# Sweep.net
KiCad netlist of a schematic drawn in Altium Designer
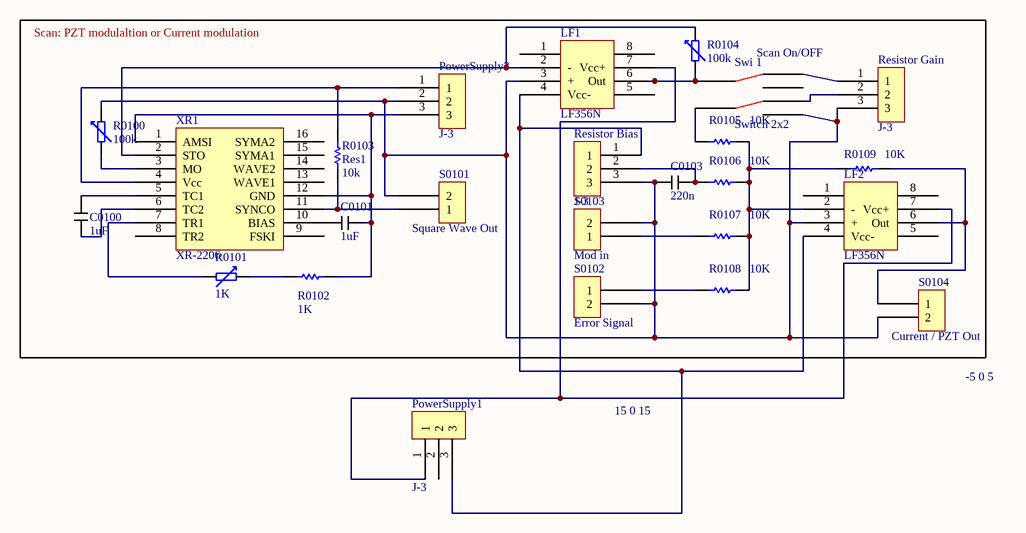
[diagram p0: Sweep.SchDoc]

(export (version "E")
  (design (tool "Eeschema 10.0.6"))
  (components
    (comp (ref "C0100") (value "1uF") (footprint "Capacitor") (libsource (lib "Schlib1") (part "Cap")))
    (comp (ref "C0101") (value "1uF") (footprint "Capacitor") (libsource (lib "Schlib1") (part "Cap")))
    (comp (ref "C0103") (value "220n") (footprint "Capacitor") (libsource (lib "Schlib1") (part "Cap")))
    (comp (ref "LF1") (value "LF356N") (footprint "DIP8") (libsource (lib "Schlib1") (part "LF356N")))
    (comp (ref "LF2") (value "LF356N") (footprint "DIP8") (libsource (lib "Schlib1") (part "LF356N")))
    (comp (ref "PowerSupply1") (value "J-3") (footprint "J3") (libsource (lib "Schlib1") (part "J-3")))
    (comp (ref "PowerSupply3") (value "J-3") (footprint "J3") (libsource (lib "") (part "J-3_2")))
    (comp (ref "R0100") (value "100k") (footprint "J3") (libsource (lib "Schlib1") (part "Res Adj")))
    (comp (ref "R0101") (value "1K") (footprint "J3") (libsource (lib "Schlib1") (part "Res Adj")))
    (comp (ref "R0102")
      (value "1K")
      (footprint "AXIAL-0.3")
      (description "Resistor")
      (fields (field (name "Comment") "Res1") (field (name "PUBLISHER") "Altium Limited"))
      (libsource (lib "Miscellaneous Devices") (part "Res1"))
    )
    (comp (ref "R0103")
      (value "Res1")
      (footprint "AXIAL-0.3")
      (description "Resistor")
      (fields (field (name "ALTIUM_VALUE") "10k") (field (name "PUBLISHER") "Altium Limited"))
      (libsource (lib "Miscellaneous Devices") (part "Res1"))
    )
    (comp (ref "R0104") (value "100k") (footprint "J3") (libsource (lib "Schlib1") (part "Res Adj")))
    (comp (ref "R0105")
      (value "10K")
      (footprint "AXIAL-0.3")
      (description "Resistor")
      (fields (field (name "Comment") "Res1") (field (name "PUBLISHER") "Altium Limited"))
      (libsource (lib "Miscellaneous Devices") (part "Res1"))
    )
    (comp (ref "R0106")
      (value "10K")
      (footprint "AXIAL-0.3")
      (description "Resistor")
      (fields (field (name "Comment") "Res1") (field (name "PUBLISHER") "Altium Limited"))
      (libsource (lib "Miscellaneous Devices") (part "Res1"))
    )
    (comp (ref "R0107")
      (value "10K")
      (footprint "AXIAL-0.3")
      (description "Resistor")
      (fields (field (name "Comment") "Res1") (field (name "PUBLISHER") "Altium Limited"))
      (libsource (lib "Miscellaneous Devices") (part "Res1"))
    )
    (comp (ref "R0108")
      (value "10K")
      (footprint "AXIAL-0.3")
      (description "Resistor")
      (fields (field (name "Comment") "Res1") (field (name "PUBLISHER") "Altium Limited"))
      (libsource (lib "Miscellaneous Devices") (part "Res1"))
    )
    (comp (ref "R0109")
      (value "10K")
      (footprint "AXIAL-0.3")
      (description "Resistor")
      (fields (field (name "Comment") "Res1") (field (name "PUBLISHER") "Altium Limited"))
      (libsource (lib "Miscellaneous Devices") (part "Res1"))
    )
    (comp (ref "Resistor Bias") (value "J-3") (footprint "J3") (libsource (lib "") (part "J-3_1")))
    (comp (ref "Resistor Gain") (value "J-3") (footprint "J3") (libsource (lib "") (part "J-3_2")))
    (comp (ref "S0101") (value "Square Wave Out") (footprint "SMA-S") (libsource (lib "") (part "SMA-S_2")))
    (comp (ref "S0102") (value "Error Signal") (footprint "SMA-S") (libsource (lib "") (part "SMA-S_3")))
    (comp (ref "S0103") (value "Mod in") (footprint "SMA-S") (libsource (lib "") (part "SMA-S_1")))
    (comp (ref "S0104")
      (value "Current / PZT Out")
      (footprint "SMA-S")
      (libsource (lib "Schlib1") (part "SMA-S"))
    )
    (comp (ref "Swi 1")
      (value "Switch 2x2")
      (footprint "Swi 2x2")
      (libsource (lib "Schlib1") (part "Switch 2x2"))
    )
    (comp (ref "XR1") (value "XR-2206") (footprint "DIP16") (libsource (lib "Schlib1") (part "XR-2206")))
  )
  (nets
    (net (code "1") (name "Net-(C0103-Pad2)") (class "Default")
      (node (ref "C0103") (pin "2") (pinfunction "2_2") (pintype "passive"))
      (node (ref "R0106") (pin "1") (pinfunction "1_1") (pintype "passive"))
      (node (ref "Resistor Bias") (pin "2") (pinfunction "2_2") (pintype "passive"))
    )
    (net (code "2") (name "Net-(LF1-+)") (class "Default")
      (node (ref "C0103") (pin "1") (pinfunction "1_1") (pintype "passive"))
      (node (ref "LF1") (pin "3") (pinfunction "+_3") (pintype "passive"))
      (node (ref "LF2") (pin "3") (pinfunction "+_3") (pintype "passive"))
      (node (ref "PowerSupply3") (pin "2") (pinfunction "2_2") (pintype "passive"))
      (node (ref "R0100") (pin "2") (pinfunction "2_2") (pintype "passive"))
      (node (ref "Resistor Bias") (pin "3") (pinfunction "3_3") (pintype "passive"))
      (node (ref "Resistor Gain") (pin "3") (pinfunction "3_3") (pintype "passive"))
      (node (ref "S0101") (pin "2") (pinfunction "2_2") (pintype "passive"))
      (node (ref "S0102") (pin "2") (pinfunction "2_2") (pintype "passive"))
      (node (ref "S0103") (pin "2") (pinfunction "2_2") (pintype "passive"))
      (node (ref "S0104") (pin "2") (pinfunction "2_2") (pintype "passive"))
      (node (ref "Swi 1") (pin "6") (pinfunction "6_6") (pintype "passive"))
    )
    (net (code "3") (name "Net-(LF1--)") (class "Default")
      (node (ref "LF1") (pin "2") (pinfunction "-_2") (pintype "passive"))
      (node (ref "R0104") (pin "2") (pinfunction "2_2") (pintype "passive"))
      (node (ref "XR1") (pin "2") (pinfunction "STO_2") (pintype "passive"))
    )
    (net (code "4") (name "Net-(LF1-Out)") (class "Default")
      (node (ref "LF1") (pin "6") (pinfunction "Out_6") (pintype "passive"))
      (node (ref "R0104") (pin "1") (pinfunction "1_1") (pintype "passive"))
      (node (ref "Swi 1") (pin "1") (pinfunction "1_1") (pintype "passive"))
    )
    (net (code "5") (name "Net-(LF1-Vcc+)") (class "Default")
      (node (ref "LF1") (pin "7") (pinfunction "Vcc+_7") (pintype "passive"))
      (node (ref "LF2") (pin "7") (pinfunction "Vcc+_7") (pintype "passive"))
      (node (ref "PowerSupply1") (pin "1") (pinfunction "1_1") (pintype "passive"))
    )
    (net (code "6") (name "Net-(LF1-Vcc-)") (class "Default")
      (node (ref "LF1") (pin "4") (pinfunction "Vcc-_4") (pintype "passive"))
      (node (ref "LF2") (pin "4") (pinfunction "Vcc-_4") (pintype "passive"))
      (node (ref "PowerSupply1") (pin "3") (pinfunction "3_3") (pintype "passive"))
      (node (ref "Resistor Bias") (pin "1") (pinfunction "1_1") (pintype "passive"))
    )
    (net (code "7") (name "Net-(LF2--)") (class "Default")
      (node (ref "LF2") (pin "2") (pinfunction "-_2") (pintype "passive"))
      (node (ref "R0105") (pin "2") (pinfunction "2_2") (pintype "passive"))
      (node (ref "R0106") (pin "2") (pinfunction "2_2") (pintype "passive"))
      (node (ref "R0107") (pin "2") (pinfunction "2_2") (pintype "passive"))
      (node (ref "R0108") (pin "2") (pinfunction "2_2") (pintype "passive"))
      (node (ref "R0109") (pin "1") (pinfunction "1_1") (pintype "passive"))
    )
    (net (code "8") (name "Net-(LF2-Out)") (class "Default")
      (node (ref "LF2") (pin "6") (pinfunction "Out_6") (pintype "passive"))
      (node (ref "R0109") (pin "2") (pinfunction "2_2") (pintype "passive"))
      (node (ref "S0104") (pin "1") (pinfunction "1_1") (pintype "passive"))
    )
    (net (code "9") (name "Net-(R0101-Pad2)") (class "Default")
      (node (ref "R0101") (pin "2") (pinfunction "2_2") (pintype "passive"))
      (node (ref "R0102") (pin "1") (pinfunction "1_1") (pintype "passive"))
    )
    (net (code "10") (name "Net-(R0105-Pad1)") (class "Default")
      (node (ref "R0105") (pin "1") (pinfunction "1_1") (pintype "passive"))
      (node (ref "Swi 1") (pin "2") (pinfunction "2_2") (pintype "passive"))
    )
    (net (code "11") (name "Net-(R0107-Pad1)") (class "Default")
      (node (ref "R0107") (pin "1") (pinfunction "1_1") (pintype "passive"))
      (node (ref "S0103") (pin "1") (pinfunction "1_1") (pintype "passive"))
    )
    (net (code "12") (name "Net-(R0108-Pad1)") (class "Default")
      (node (ref "R0108") (pin "1") (pinfunction "1_1") (pintype "passive"))
      (node (ref "S0102") (pin "1") (pinfunction "1_1") (pintype "passive"))
    )
    (net (code "13") (name "Net-(Resistor Gain-Pad1)") (class "Default")
      (node (ref "Resistor Gain") (pin "1") (pinfunction "1_1") (pintype "passive"))
      (node (ref "Swi 1") (pin "3") (pinfunction "3_3") (pintype "passive"))
    )
    (net (code "14") (name "Net-(Resistor Gain-Pad2)") (class "Default")
      (node (ref "Resistor Gain") (pin "2") (pinfunction "2_2") (pintype "passive"))
      (node (ref "Swi 1") (pin "4") (pinfunction "4_4") (pintype "passive"))
    )
    (net (code "15") (name "Net-(XR1-AMSI)") (class "Default")
      (node (ref "C0101") (pin "2") (pinfunction "2_2") (pintype "passive"))
      (node (ref "PowerSupply3") (pin "3") (pinfunction "3_3") (pintype "passive"))
      (node (ref "R0102") (pin "2") (pinfunction "2_2") (pintype "passive"))
      (node (ref "XR1") (pin "1") (pinfunction "AMSI_1") (pintype "passive"))
      (node (ref "XR1") (pin "12") (pinfunction "GND_12") (pintype "passive"))
    )
    (net (code "16") (name "Net-(XR1-BIAS)") (class "Default")
      (node (ref "C0101") (pin "1") (pinfunction "1_1") (pintype "passive"))
      (node (ref "XR1") (pin "10") (pinfunction "BIAS_10") (pintype "passive"))
    )
    (net (code "17") (name "Net-(XR1-MO)") (class "Default")
      (node (ref "R0100") (pin "1") (pinfunction "1_1") (pintype "passive"))
      (node (ref "XR1") (pin "3") (pinfunction "MO_3") (pintype "passive"))
    )
    (net (code "18") (name "Net-(XR1-SYNCO)") (class "Default")
      (node (ref "R0103") (pin "1") (pinfunction "1_1") (pintype "passive"))
      (node (ref "S0101") (pin "1") (pinfunction "1_1") (pintype "passive"))
      (node (ref "XR1") (pin "11") (pinfunction "SYNCO_11") (pintype "passive"))
    )
    (net (code "19") (name "Net-(XR1-TC1)") (class "Default")
      (node (ref "C0100") (pin "1") (pinfunction "1_1") (pintype "passive"))
      (node (ref "XR1") (pin "5") (pinfunction "TC1_5") (pintype "passive"))
    )
    (net (code "20") (name "Net-(XR1-TC2)") (class "Default")
      (node (ref "C0100") (pin "2") (pinfunction "2_2") (pintype "passive"))
      (node (ref "XR1") (pin "6") (pinfunction "TC2_6") (pintype "passive"))
    )
    (net (code "21") (name "Net-(XR1-TR1)") (class "Default")
      (node (ref "R0101") (pin "1") (pinfunction "1_1") (pintype "passive"))
      (node (ref "XR1") (pin "7") (pinfunction "TR1_7") (pintype "passive"))
    )
    (net (code "22") (name "Net-(XR1-Vcc)") (class "Default")
      (node (ref "PowerSupply3") (pin "1") (pinfunction "1_1") (pintype "passive"))
      (node (ref "R0103") (pin "2") (pinfunction "2_2") (pintype "passive"))
      (node (ref "XR1") (pin "4") (pinfunction "Vcc_4") (pintype "passive"))
    )
    (net (code "23") (name "unconnected-(LF1-N.C.-Pad8)") (class "Default")
      (node (ref "LF1") (pin "8") (pinfunction "N.C._8") (pintype "passive"))
    )
    (net (code "24") (name "unconnected-(LF1-Offset_Null-Pad1)") (class "Default")
      (node (ref "LF1") (pin "1") (pinfunction "Offset_Null_1") (pintype "passive"))
    )
    (net (code "25") (name "unconnected-(LF1-Offset_Null2-Pad5)") (class "Default")
      (node (ref "LF1") (pin "5") (pinfunction "Offset_Null2_5") (pintype "passive"))
    )
    (net (code "26") (name "unconnected-(LF2-N.C.-Pad8)") (class "Default")
      (node (ref "LF2") (pin "8") (pinfunction "N.C._8") (pintype "passive"))
    )
    (net (code "27") (name "unconnected-(LF2-Offset_Null-Pad1)") (class "Default")
      (node (ref "LF2") (pin "1") (pinfunction "Offset_Null_1") (pintype "passive"))
    )
    (net (code "28") (name "unconnected-(LF2-Offset_Null2-Pad5)") (class "Default")
      (node (ref "LF2") (pin "5") (pinfunction "Offset_Null2_5") (pintype "passive"))
    )
    (net (code "29") (name "unconnected-(PowerSupply1-Pad2)") (class "Default")
      (node (ref "PowerSupply1") (pin "2") (pinfunction "2_2") (pintype "passive"))
    )
    (net (code "30") (name "unconnected-(Swi 1-Pad5)") (class "Default")
      (node (ref "Swi 1") (pin "5") (pinfunction "5_5") (pintype "passive"))
    )
    (net (code "31") (name "unconnected-(XR1-FSKI-Pad9)") (class "Default")
      (node (ref "XR1") (pin "9") (pinfunction "FSKI_9") (pintype "passive"))
    )
    (net (code "32") (name "unconnected-(XR1-SYMA1-Pad15)") (class "Default")
      (node (ref "XR1") (pin "15") (pinfunction "SYMA1_15") (pintype "passive"))
    )
    (net (code "33") (name "unconnected-(XR1-SYMA2-Pad16)") (class "Default")
      (node (ref "XR1") (pin "16") (pinfunction "SYMA2_16") (pintype "passive"))
    )
    (net (code "34") (name "unconnected-(XR1-TR2-Pad8)") (class "Default")
      (node (ref "XR1") (pin "8") (pinfunction "TR2_8") (pintype "passive"))
    )
    (net (code "35") (name "unconnected-(XR1-WAVE1-Pad13)") (class "Default")
      (node (ref "XR1") (pin "13") (pinfunction "WAVE1_13") (pintype "passive"))
    )
    (net (code "36") (name "unconnected-(XR1-WAVE2-Pad14)") (class "Default")
      (node (ref "XR1") (pin "14") (pinfunction "WAVE2_14") (pintype "passive"))
    )
  )
)
